# rp3a0-mini-wireless-sd.net
KiCad netlist of a schematic drawn in Altium Designer
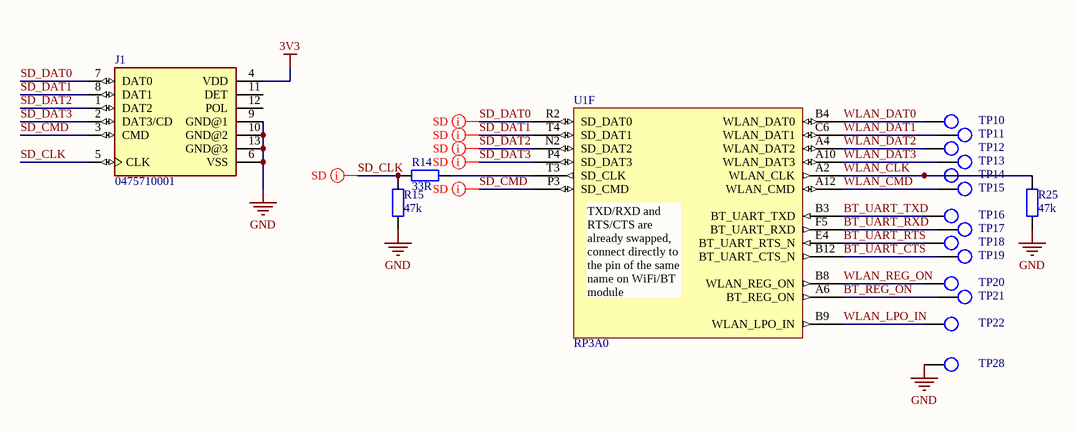
[diagram p0: rp3a0-mini-wireless-sd.SchDoc]

(export (version "E")
  (design (tool "Eeschema 10.0.6"))
  (components
    (comp (ref "J1")
      (value "0475710001")
      (footprint "MOLEX_0475710001")
      (description "9 _8 + 1_ Position Card Connector Secure Digital - microSDâ„¢ Surface Mount, Right Angle Gold")
      (fields (field (name "MF") "Molex"))
      (libsource (lib "custom-lib") (part "0475710001"))
    )
    (comp (ref "R14")
      (value "33R")
      (footprint "RES-0402-SML")
      (description "Resistor")
      (fields (field (name "Comment") "Res SMD"))
      (libsource (lib "") (part "Res SMD_1"))
    )
    (comp (ref "R15")
      (value "47k")
      (footprint "RES-0402-SML")
      (description "Resistor")
      (fields (field (name "Comment") "Res SMD"))
      (libsource (lib "custom-lib") (part "Res SMD"))
    )
    (comp (ref "R25")
      (value "47k")
      (footprint "RES-0402-SML")
      (description "Resistor")
      (fields (field (name "Comment") "Res SMD"))
      (libsource (lib "custom-lib") (part "Res SMD"))
    )
    (comp (ref "TP10")
      (value "TEST_POINT")
      (footprint "TEST_POINT_1.2MM")
      (description "Test point")
      (libsource (lib "custom-lib") (part "TEST_POINT"))
    )
    (comp (ref "TP11")
      (value "TEST_POINT")
      (footprint "TEST_POINT_1.2MM")
      (description "Test point")
      (libsource (lib "custom-lib") (part "TEST_POINT"))
    )
    (comp (ref "TP12")
      (value "TEST_POINT")
      (footprint "TEST_POINT_1.2MM")
      (description "Test point")
      (libsource (lib "custom-lib") (part "TEST_POINT"))
    )
    (comp (ref "TP13")
      (value "TEST_POINT")
      (footprint "TEST_POINT_1.2MM")
      (description "Test point")
      (libsource (lib "custom-lib") (part "TEST_POINT"))
    )
    (comp (ref "TP14")
      (value "TEST_POINT")
      (footprint "TEST_POINT_1.2MM")
      (description "Test point")
      (libsource (lib "custom-lib") (part "TEST_POINT"))
    )
    (comp (ref "TP15")
      (value "TEST_POINT")
      (footprint "TEST_POINT_1.2MM")
      (description "Test point")
      (libsource (lib "custom-lib") (part "TEST_POINT"))
    )
    (comp (ref "TP16")
      (value "TEST_POINT")
      (footprint "TEST_POINT_1.2MM")
      (description "Test point")
      (libsource (lib "custom-lib") (part "TEST_POINT"))
    )
    (comp (ref "TP17")
      (value "TEST_POINT")
      (footprint "TEST_POINT_1.2MM")
      (description "Test point")
      (libsource (lib "custom-lib") (part "TEST_POINT"))
    )
    (comp (ref "TP18")
      (value "TEST_POINT")
      (footprint "TEST_POINT_1.2MM")
      (description "Test point")
      (libsource (lib "custom-lib") (part "TEST_POINT"))
    )
    (comp (ref "TP19")
      (value "TEST_POINT")
      (footprint "TEST_POINT_1.2MM")
      (description "Test point")
      (libsource (lib "custom-lib") (part "TEST_POINT"))
    )
    (comp (ref "TP20")
      (value "TEST_POINT")
      (footprint "TEST_POINT_1.2MM")
      (description "Test point")
      (libsource (lib "custom-lib") (part "TEST_POINT"))
    )
    (comp (ref "TP21")
      (value "TEST_POINT")
      (footprint "TEST_POINT_1.2MM")
      (description "Test point")
      (libsource (lib "custom-lib") (part "TEST_POINT"))
    )
    (comp (ref "TP22")
      (value "TEST_POINT")
      (footprint "TEST_POINT_1.2MM")
      (description "Test point")
      (libsource (lib "custom-lib") (part "TEST_POINT"))
    )
    (comp (ref "TP28")
      (value "TEST_POINT")
      (footprint "TEST_POINT_1.2MM")
      (description "Test point")
      (libsource (lib "custom-lib") (part "TEST_POINT"))
    )
    (comp (ref "U1") (value "RP3A0") (footprint "RP3A0-BGA") (libsource (lib "rp3a0") (part "RP3A0")))
  )
  (nets
    (net (code "1") (name "/BT_REG_ON") (class "Default")
      (node (ref "TP21") (pin "TP") (pintype "passive"))
      (node (ref "U1") (pin "A6") (pinfunction "BT_REG_ON_A6") (pintype "output"))
    )
    (net (code "2") (name "/BT_UART_CTS") (class "Default")
      (node (ref "TP19") (pin "TP") (pintype "passive"))
      (node (ref "U1") (pin "B12") (pinfunction "BT_UART_CTS_N_B12") (pintype "output"))
    )
    (net (code "3") (name "/BT_UART_RTS") (class "Default")
      (node (ref "TP18") (pin "TP") (pintype "passive"))
      (node (ref "U1") (pin "E4") (pinfunction "BT_UART_RTS_N_E4") (pintype "input"))
    )
    (net (code "4") (name "/BT_UART_RXD") (class "Default")
      (node (ref "TP17") (pin "TP") (pintype "passive"))
      (node (ref "U1") (pin "F5") (pinfunction "BT_UART_RXD_F5") (pintype "output"))
    )
    (net (code "5") (name "/BT_UART_TXD") (class "Default")
      (node (ref "TP16") (pin "TP") (pintype "passive"))
      (node (ref "U1") (pin "B3") (pinfunction "BT_UART_TXD_B3") (pintype "input"))
    )
    (net (code "6") (name "/SD_CLK") (class "Default")
      (node (ref "J1") (pin "5") (pinfunction "CLK_5") (pintype "bidirectional"))
      (node (ref "R14") (pin "1") (pinfunction "1_1") (pintype "passive"))
      (node (ref "R15") (pin "2") (pinfunction "2_2") (pintype "passive"))
    )
    (net (code "7") (name "/SD_CMD") (class "Default")
      (node (ref "J1") (pin "3") (pinfunction "CMD_3") (pintype "bidirectional"))
      (node (ref "U1") (pin "P3") (pinfunction "SD_CMD_P3") (pintype "bidirectional"))
    )
    (net (code "8") (name "/SD_DAT0") (class "Default")
      (node (ref "J1") (pin "7") (pinfunction "DAT0_7") (pintype "bidirectional"))
      (node (ref "U1") (pin "R2") (pinfunction "SD_DAT0_R2") (pintype "bidirectional"))
    )
    (net (code "9") (name "/SD_DAT1") (class "Default")
      (node (ref "J1") (pin "8") (pinfunction "DAT1_8") (pintype "bidirectional"))
      (node (ref "U1") (pin "T4") (pinfunction "SD_DAT1_T4") (pintype "bidirectional"))
    )
    (net (code "10") (name "/SD_DAT2") (class "Default")
      (node (ref "J1") (pin "1") (pinfunction "DAT2_1") (pintype "bidirectional"))
      (node (ref "U1") (pin "N2") (pinfunction "SD_DAT2_N2") (pintype "bidirectional"))
    )
    (net (code "11") (name "/SD_DAT3") (class "Default")
      (node (ref "J1") (pin "2") (pinfunction "DAT3/CD_2") (pintype "bidirectional"))
      (node (ref "U1") (pin "P4") (pinfunction "SD_DAT3_P4") (pintype "bidirectional"))
    )
    (net (code "12") (name "/WLAN_CLK") (class "Default")
      (node (ref "R25") (pin "2") (pinfunction "2_2") (pintype "passive"))
      (node (ref "TP14") (pin "TP") (pintype "passive"))
      (node (ref "U1") (pin "A2") (pinfunction "WLAN_CLK_A2") (pintype "output"))
    )
    (net (code "13") (name "/WLAN_CMD") (class "Default")
      (node (ref "TP15") (pin "TP") (pintype "passive"))
      (node (ref "U1") (pin "A12") (pinfunction "WLAN_CMD_A12") (pintype "bidirectional"))
    )
    (net (code "14") (name "/WLAN_DAT0") (class "Default")
      (node (ref "TP10") (pin "TP") (pintype "passive"))
      (node (ref "U1") (pin "B4") (pinfunction "WLAN_DAT0_B4") (pintype "bidirectional"))
    )
    (net (code "15") (name "/WLAN_DAT1") (class "Default")
      (node (ref "TP11") (pin "TP") (pintype "passive"))
      (node (ref "U1") (pin "C6") (pinfunction "WLAN_DAT1_C6") (pintype "bidirectional"))
    )
    (net (code "16") (name "/WLAN_DAT2") (class "Default")
      (node (ref "TP12") (pin "TP") (pintype "passive"))
      (node (ref "U1") (pin "A4") (pinfunction "WLAN_DAT2_A4") (pintype "bidirectional"))
    )
    (net (code "17") (name "/WLAN_DAT3") (class "Default")
      (node (ref "TP13") (pin "TP") (pintype "passive"))
      (node (ref "U1") (pin "A10") (pinfunction "WLAN_DAT3_A10") (pintype "bidirectional"))
    )
    (net (code "18") (name "/WLAN_LPO_IN") (class "Default")
      (node (ref "TP22") (pin "TP") (pintype "passive"))
      (node (ref "U1") (pin "B9") (pinfunction "WLAN_LPO_IN_B9") (pintype "output"))
    )
    (net (code "19") (name "/WLAN_REG_ON") (class "Default")
      (node (ref "TP20") (pin "TP") (pintype "passive"))
      (node (ref "U1") (pin "B8") (pinfunction "WLAN_REG_ON_B8") (pintype "output"))
    )
    (net (code "20") (name "3V3") (class "Default")
      (node (ref "J1") (pin "4") (pinfunction "VDD_4") (pintype "power_in"))
    )
    (net (code "21") (name "GND") (class "Default")
      (node (ref "J1") (pin "10") (pinfunction "GND@2_10") (pintype "power_in"))
      (node (ref "J1") (pin "13") (pinfunction "GND@3_13") (pintype "power_in"))
      (node (ref "J1") (pin "6") (pinfunction "VSS_6") (pintype "power_in"))
      (node (ref "J1") (pin "9") (pinfunction "GND@1_9") (pintype "power_in"))
      (node (ref "R15") (pin "1") (pinfunction "1_1") (pintype "passive"))
      (node (ref "R25") (pin "1") (pinfunction "1_1") (pintype "passive"))
      (node (ref "TP28") (pin "TP") (pintype "passive"))
    )
    (net (code "22") (name "Net-(U1F-SD_CLK)") (class "Default")
      (node (ref "R14") (pin "2") (pinfunction "2_2") (pintype "passive"))
      (node (ref "U1") (pin "T3") (pinfunction "SD_CLK_T3") (pintype "output"))
    )
    (net (code "23") (name "unconnected-(J1-DET-Pad11)") (class "Default")
      (node (ref "J1") (pin "11") (pinfunction "DET_11") (pintype "passive"))
    )
    (net (code "24") (name "unconnected-(J1-POL-Pad12)") (class "Default")
      (node (ref "J1") (pin "12") (pinfunction "POL_12") (pintype "passive"))
    )
  )
)
